# Power_SchematicWITHFOOTPRINTS.net
KiCad netlist of a schematic drawn in Altium Designer
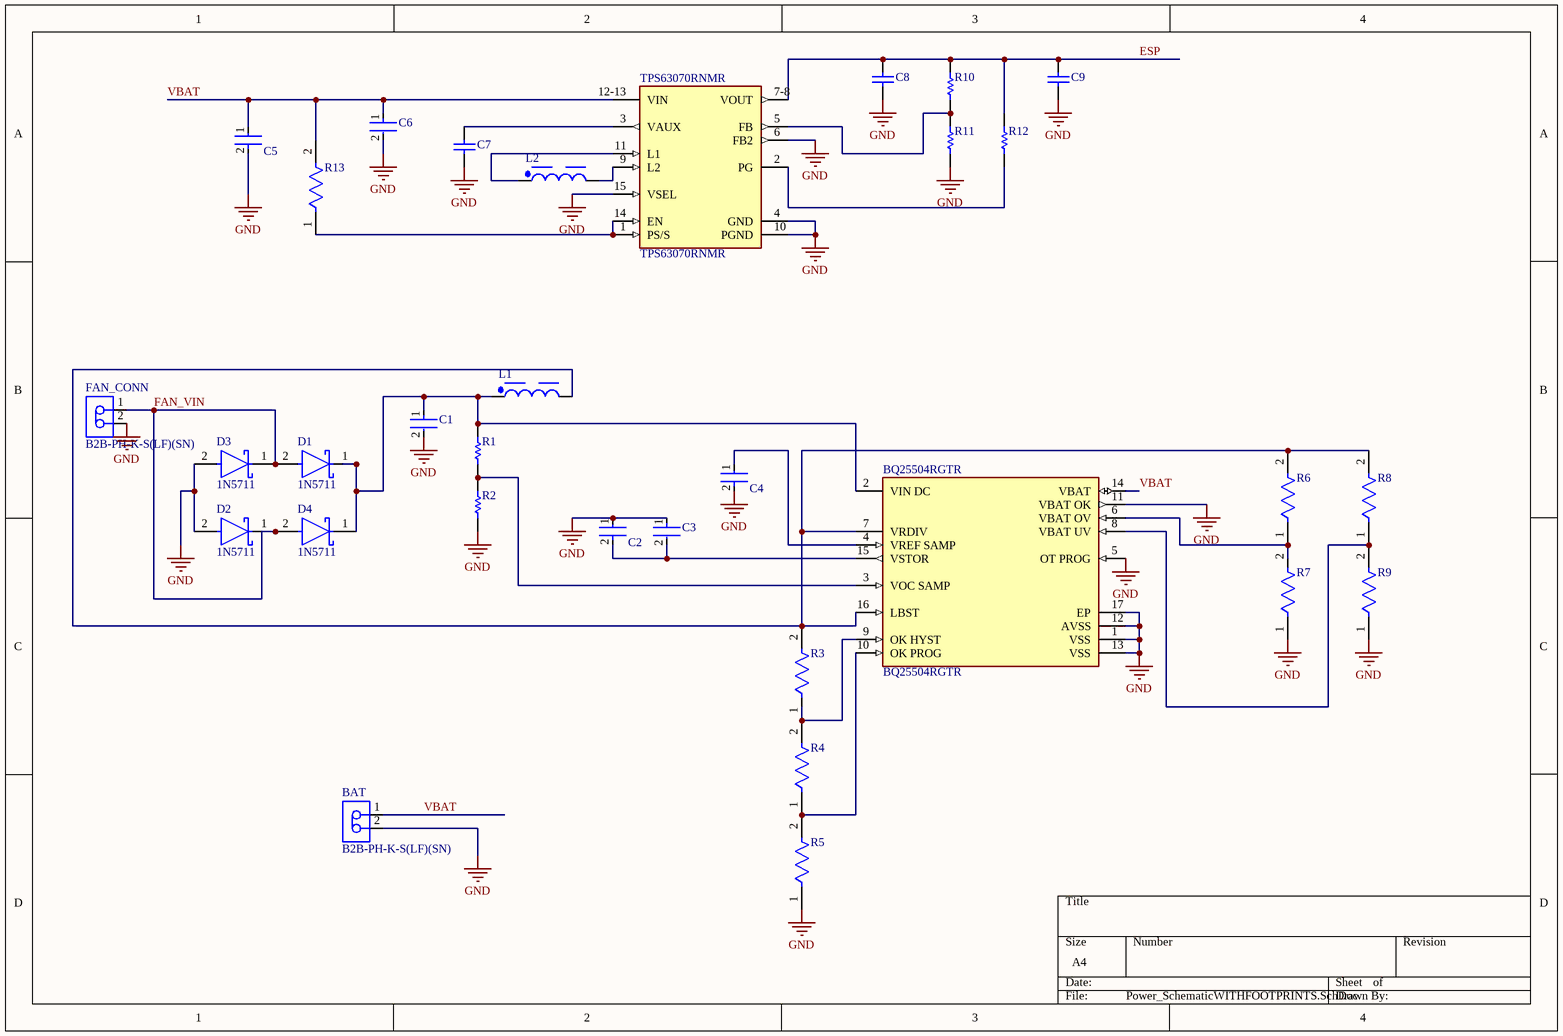
[diagram p0: Power_SchematicWITHFOOTPRINTS.SchDoc]

(export (version "E")
  (design (tool "Eeschema 10.0.6"))
  (components
    (comp (ref "BAT")
      (value "B2B-PH-K-S(LF)(SN)")
      (footprint "JST-B2B-PH-K-S_V")
      (fields (field (name "MANUFACTURER") "JST"))
      (libsource (lib "Altium Content Vault") (part "CN-2P-F-QF2"))
    )
    (comp (ref "BQ25504RGTR")
      (value "BQ25504RGTR")
      (footprint "FP-RGT0016C-IPC_B")
      (description "IC ENERGY HARV CTRLR BATT 16QFN")
      (libsource (lib "Altium Content Vault") (part "e5d8dc60ace48e978414c9197b193df"))
    )
    (comp (ref "C1")
      (value "RCER71E475K2DBH03A")
      (footprint "FP-RCE2A2-MFG")
      (description "Cap Ceramic 4.7uF 25V X7R ±10% Radial 2.5mm +125°C Automotive Ammo Pack")
      (fields (field (name "TOLERANCE") "10%"))
      (libsource (lib "Altium Content Vault") (part "b4654b650e69147ec39a6b967a45e02"))
    )
    (comp (ref "C2")
      (value "562R5GAS10")
      (footprint "FP-562R5GAS10-MFG")
      (description "CAP CER 10000PF 1KV Z5U RADIAL")
      (fields (field (name "TOLERANCE") "20%") (field (name "VOLTAGE") "1kV"))
      (libsource (lib "Altium Content Vault") (part "6d4d395cd7362dd47ce0157d173177e"))
    )
    (comp (ref "C3")
      (value "RCER71E475K2DBH03A")
      (footprint "FP-RCE2A2-MFG")
      (description "Cap Ceramic 4.7uF 25V X7R ±10% Radial 2.5mm +125°C Automotive Ammo Pack")
      (fields (field (name "TOLERANCE") "10%"))
      (libsource (lib "Altium Content Vault") (part "b4654b650e69147ec39a6b967a45e02"))
    )
    (comp (ref "C4")
      (value "562R5GAS10")
      (footprint "FP-562R5GAS10-MFG")
      (description "CAP CER 10000PF 1KV Z5U RADIAL")
      (fields (field (name "TOLERANCE") "20%") (field (name "VOLTAGE") "1kV"))
      (libsource (lib "Altium Content Vault") (part "6d4d395cd7362dd47ce0157d173177e"))
    )
    (comp (ref "C5")
      (value "562R5GAS10")
      (footprint "FP-562R5GAS10-MFG")
      (description "CAP CER 10000PF 1KV Z5U RADIAL")
      (fields (field (name "TOLERANCE") "20%") (field (name "VOLTAGE") "1kV"))
      (libsource (lib "Altium Content Vault") (part "6d4d395cd7362dd47ce0157d173177e"))
    )
    (comp (ref "C6")
      (value "RCER71E106K3DBH03A")
      (footprint "FP-RCE3DB-MFG")
      (description "Cap Ceramic 10uF 25V X7R ±10% Radial 2.5mm +125°C Automotive Ammo Pack")
      (fields (field (name "TOLERANCE") "10%"))
      (libsource (lib "Altium Content Vault") (part "b4654b650e69147ec39a6b967a45e02"))
    )
    (comp (ref "C7")
      (value "C320C104K5R5TA")
      (footprint "CAPR51-254-508X318X736")
      (libsource (lib "Altium Content Vault") (part "CAP-NP-2"))
    )
    (comp (ref "C8")
      (value "C320C104K5R5TA")
      (footprint "CAPR51-254-508X318X736")
      (libsource (lib "Altium Content Vault") (part "CAP-NP-2"))
    )
    (comp (ref "C9")
      (value "C320C104K5R5TA")
      (footprint "CAPR51-254-508X318X736")
      (libsource (lib "Altium Content Vault") (part "CAP-NP-2"))
    )
    (comp (ref "D1")
      (value "1N5711")
      (footprint "FP-DO-35-MFG")
      (description "RF DIODE SCHOTTKY 70V 430MW DO35")
      (fields
        (field (name "MANUFACTURER") "STMicroelectronics")
        (field (name "OCTOPART") "https://octopart.com/1n5711-stmicroelectronics-55399277")
      )
      (libsource (lib "Altium Content Vault") (part "1d6ec82d83fb6aee721767c19dac4b9"))
    )
    (comp (ref "D2")
      (value "1N5711")
      (footprint "FP-DO-35-MFG")
      (description "RF DIODE SCHOTTKY 70V 430MW DO35")
      (fields
        (field (name "MANUFACTURER") "STMicroelectronics")
        (field (name "OCTOPART") "https://octopart.com/1n5711-stmicroelectronics-55399277")
      )
      (libsource (lib "Altium Content Vault") (part "1d6ec82d83fb6aee721767c19dac4b9"))
    )
    (comp (ref "D3")
      (value "1N5711")
      (footprint "FP-DO-35-MFG")
      (description "RF DIODE SCHOTTKY 70V 430MW DO35")
      (fields
        (field (name "MANUFACTURER") "STMicroelectronics")
        (field (name "OCTOPART") "https://octopart.com/1n5711-stmicroelectronics-55399277")
      )
      (libsource (lib "Altium Content Vault") (part "1d6ec82d83fb6aee721767c19dac4b9"))
    )
    (comp (ref "D4")
      (value "1N5711")
      (footprint "FP-DO-35-MFG")
      (description "RF DIODE SCHOTTKY 70V 430MW DO35")
      (fields
        (field (name "MANUFACTURER") "STMicroelectronics")
        (field (name "OCTOPART") "https://octopart.com/1n5711-stmicroelectronics-55399277")
      )
      (libsource (lib "Altium Content Vault") (part "1d6ec82d83fb6aee721767c19dac4b9"))
    )
    (comp (ref "FAN_CONN")
      (value "B2B-PH-K-S(LF)(SN)")
      (footprint "JST-B2B-PH-K-S_V")
      (fields (field (name "MANUFACTURER") "JST"))
      (libsource (lib "Altium Content Vault") (part "CN-2P-F-QF2"))
    )
    (comp (ref "L1")
      (value "7447471033")
      (footprint "WE-TIS_1111")
      (fields (field (name "TOLERANCE") "20%"))
      (libsource (lib "Altium Content Vault") (part "Inductor - 2"))
    )
    (comp (ref "L2")
      (value "744741221")
      (footprint "WE-TI_8055")
      (libsource (lib "Altium Content Vault") (part "Inductor - 2"))
    )
    (comp (ref "R1")
      (value "PR02000206202JA100")
      (footprint "VISH-A1-2_V2")
      (description "Power Metal Film Leaded Resistor, 62 KOhm +/-5%, 2 W, 2-Pin THD, RoHS, Ammo Pack")
      (fields (field (name "TOLERANCE") "+/-5%") (field (name "POWER") "2 W"))
      (libsource (lib "Altium Content Vault") (part "VISH-RES-2"))
    )
    (comp (ref "R2")
      (value "PR02000206202JA100")
      (footprint "VISH-A1-2_V2")
      (description "Power Metal Film Leaded Resistor, 62 KOhm +/-5%, 2 W, 2-Pin THD, RoHS, Ammo Pack")
      (fields (field (name "TOLERANCE") "+/-5%") (field (name "POWER") "2 W"))
      (libsource (lib "Altium Content Vault") (part "VISH-RES-2"))
    )
    (comp (ref "R3")
      (value "MRS25000C1000FRP00")
      (footprint "FP-MRS25-MFG")
      (fields (field (name "TOLERANCE") "1%"))
      (libsource (lib "Altium Content Vault") (part "1029c3af85768c4190bb7ad29bc67b5"))
    )
    (comp (ref "R4")
      (value "MRS25000C1000FRP00")
      (footprint "FP-MRS25-MFG")
      (fields (field (name "TOLERANCE") "1%"))
      (libsource (lib "Altium Content Vault") (part "1029c3af85768c4190bb7ad29bc67b5"))
    )
    (comp (ref "R5")
      (value "MRS25000C1000FRP00")
      (footprint "FP-MRS25-MFG")
      (fields (field (name "TOLERANCE") "1%"))
      (libsource (lib "Altium Content Vault") (part "1029c3af85768c4190bb7ad29bc67b5"))
    )
    (comp (ref "R6")
      (value "MRS25000C1000FRP00")
      (footprint "FP-MRS25-MFG")
      (fields (field (name "TOLERANCE") "1%"))
      (libsource (lib "Altium Content Vault") (part "1029c3af85768c4190bb7ad29bc67b5"))
    )
    (comp (ref "R7")
      (value "MRS25000C1000FRP00")
      (footprint "FP-MRS25-MFG")
      (fields (field (name "TOLERANCE") "1%"))
      (libsource (lib "Altium Content Vault") (part "1029c3af85768c4190bb7ad29bc67b5"))
    )
    (comp (ref "R8")
      (value "MRS25000C1000FRP00")
      (footprint "FP-MRS25-MFG")
      (fields (field (name "TOLERANCE") "1%"))
      (libsource (lib "Altium Content Vault") (part "1029c3af85768c4190bb7ad29bc67b5"))
    )
    (comp (ref "R9")
      (value "MRS25000C1000FRP00")
      (footprint "FP-MRS25-MFG")
      (fields (field (name "TOLERANCE") "1%"))
      (libsource (lib "Altium Content Vault") (part "1029c3af85768c4190bb7ad29bc67b5"))
    )
    (comp (ref "R10")
      (value "PR02000206202JA100")
      (footprint "VISH-A1-2_V2")
      (description "Power Metal Film Leaded Resistor, 62 KOhm +/-5%, 2 W, 2-Pin THD, RoHS, Ammo Pack")
      (fields (field (name "TOLERANCE") "+/-5%") (field (name "POWER") "2 W"))
      (libsource (lib "Altium Content Vault") (part "VISH-RES-2"))
    )
    (comp (ref "R11")
      (value "PR02000206202JA100")
      (footprint "VISH-A1-2_V2")
      (description "Power Metal Film Leaded Resistor, 62 KOhm +/-5%, 2 W, 2-Pin THD, RoHS, Ammo Pack")
      (fields (field (name "TOLERANCE") "+/-5%") (field (name "POWER") "2 W"))
      (libsource (lib "Altium Content Vault") (part "VISH-RES-2"))
    )
    (comp (ref "R12")
      (value "PR02000206202JA100")
      (footprint "VISH-A1-2_V2")
      (description "Power Metal Film Leaded Resistor, 62 KOhm +/-5%, 2 W, 2-Pin THD, RoHS, Ammo Pack")
      (fields (field (name "TOLERANCE") "+/-5%") (field (name "POWER") "2 W"))
      (libsource (lib "Altium Content Vault") (part "VISH-RES-2"))
    )
    (comp (ref "R13")
      (value "MRS25000C1002FCT00")
      (footprint "FP-MRS25-MFG")
      (fields (field (name "TOLERANCE") "1%"))
      (libsource (lib "Altium Content Vault") (part "1029c3af85768c4190bb7ad29bc67b5"))
    )
    (comp (ref "TPS63070RNMR")
      (value "TPS63070RNMR")
      (footprint "FP-RNM0015A-MFG")
      (description "IC REG BCK BST ADJ 3.6A 15VQFN")
      (libsource (lib "Altium Content Vault") (part "a4d5b1e6901c8533e317c4aea8f1b15"))
    )
  )
  (nets
    (net (code "1") (name "/ESP") (class "Default")
      (node (ref "C8") (pin "2") (pinfunction "2_2") (pintype "passive"))
      (node (ref "C9") (pin "2") (pinfunction "2_2") (pintype "passive"))
      (node (ref "R10") (pin "2") (pinfunction "2_2") (pintype "passive"))
      (node (ref "R12") (pin "2") (pinfunction "2_2") (pintype "passive"))
      (node (ref "TPS63070RNMR") (pin "7-8") (pinfunction "VOUT_7-8") (pintype "output"))
    )
    (net (code "2") (name "/FAN_VIN") (class "Default")
      (node (ref "D1") (pin "2") (pinfunction "A_2") (pintype "passive"))
      (node (ref "D2") (pin "1") (pinfunction "C_1") (pintype "passive"))
      (node (ref "D3") (pin "1") (pinfunction "C_1") (pintype "passive"))
      (node (ref "D4") (pin "2") (pinfunction "A_2") (pintype "passive"))
      (node (ref "FAN_CONN") (pin "1") (pinfunction "1_1") (pintype "passive"))
    )
    (net (code "3") (name "/VBAT") (class "Default")
      (node (ref "BAT") (pin "1") (pinfunction "1_1") (pintype "passive"))
      (node (ref "BQ25504RGTR") (pin "14") (pinfunction "VBAT_14") (pintype "bidirectional"))
      (node (ref "C5") (pin "1") (pinfunction "1_1") (pintype "passive"))
      (node (ref "C6") (pin "1") (pinfunction "1_1") (pintype "passive"))
      (node (ref "R13") (pin "2") (pinfunction "2_2") (pintype "passive"))
      (node (ref "TPS63070RNMR") (pin "12-13") (pinfunction "VIN_12-13") (pintype "power_in"))
    )
    (net (code "4") (name "GND") (class "Default")
      (node (ref "BAT") (pin "2") (pinfunction "2_2") (pintype "passive"))
      (node (ref "BQ25504RGTR") (pin "1") (pinfunction "VSS_1") (pintype "power_in"))
      (node (ref "BQ25504RGTR") (pin "11") (pinfunction "VBAT_OK_11") (pintype "output"))
      (node (ref "BQ25504RGTR") (pin "12") (pinfunction "AVSS_12") (pintype "power_in"))
      (node (ref "BQ25504RGTR") (pin "13") (pinfunction "VSS_13") (pintype "power_in"))
      (node (ref "BQ25504RGTR") (pin "17") (pinfunction "EP_17") (pintype "passive"))
      (node (ref "BQ25504RGTR") (pin "5") (pinfunction "OT_PROG_5") (pintype "input"))
      (node (ref "C1") (pin "2") (pinfunction "2_2") (pintype "passive"))
      (node (ref "C2") (pin "1") (pinfunction "1_1") (pintype "passive"))
      (node (ref "C3") (pin "1") (pinfunction "1_1") (pintype "passive"))
      (node (ref "C4") (pin "2") (pinfunction "2_2") (pintype "passive"))
      (node (ref "C5") (pin "2") (pinfunction "2_2") (pintype "passive"))
      (node (ref "C6") (pin "2") (pinfunction "2_2") (pintype "passive"))
      (node (ref "C7") (pin "1") (pinfunction "1_1") (pintype "passive"))
      (node (ref "C8") (pin "1") (pinfunction "1_1") (pintype "passive"))
      (node (ref "C9") (pin "1") (pinfunction "1_1") (pintype "passive"))
      (node (ref "D2") (pin "2") (pinfunction "A_2") (pintype "passive"))
      (node (ref "D3") (pin "2") (pinfunction "A_2") (pintype "passive"))
      (node (ref "FAN_CONN") (pin "2") (pinfunction "2_2") (pintype "passive"))
      (node (ref "R11") (pin "1") (pinfunction "1_1") (pintype "passive"))
      (node (ref "R2") (pin "1") (pinfunction "1_1") (pintype "passive"))
      (node (ref "R5") (pin "1") (pinfunction "1_1") (pintype "passive"))
      (node (ref "R7") (pin "1") (pinfunction "1_1") (pintype "passive"))
      (node (ref "R9") (pin "1") (pinfunction "1_1") (pintype "passive"))
      (node (ref "TPS63070RNMR") (pin "10") (pinfunction "PGND_10") (pintype "power_in"))
      (node (ref "TPS63070RNMR") (pin "15") (pinfunction "VSEL_15") (pintype "input"))
      (node (ref "TPS63070RNMR") (pin "4") (pinfunction "GND_4") (pintype "power_in"))
      (node (ref "TPS63070RNMR") (pin "6") (pinfunction "FB2_6") (pintype "output"))
    )
    (net (code "5") (name "Net-(BQ25504RGTR-LBST)") (class "Default")
      (node (ref "BQ25504RGTR") (pin "16") (pinfunction "LBST_16") (pintype "input"))
      (node (ref "BQ25504RGTR") (pin "7") (pinfunction "VRDIV_7") (pintype "power_in"))
      (node (ref "L1") (pin "2") (pinfunction "2_2") (pintype "passive"))
      (node (ref "R3") (pin "2") (pinfunction "2_2") (pintype "passive"))
      (node (ref "R6") (pin "2") (pinfunction "2_2") (pintype "passive"))
      (node (ref "R8") (pin "2") (pinfunction "2_2") (pintype "passive"))
    )
    (net (code "6") (name "Net-(BQ25504RGTR-OK_HYST)") (class "Default")
      (node (ref "BQ25504RGTR") (pin "9") (pinfunction "OK_HYST_9") (pintype "input"))
      (node (ref "R3") (pin "1") (pinfunction "1_1") (pintype "passive"))
      (node (ref "R4") (pin "2") (pinfunction "2_2") (pintype "passive"))
    )
    (net (code "7") (name "Net-(BQ25504RGTR-OK_PROG)") (class "Default")
      (node (ref "BQ25504RGTR") (pin "10") (pinfunction "OK_PROG_10") (pintype "input"))
      (node (ref "R4") (pin "1") (pinfunction "1_1") (pintype "passive"))
      (node (ref "R5") (pin "2") (pinfunction "2_2") (pintype "passive"))
    )
    (net (code "8") (name "Net-(BQ25504RGTR-VBAT_OV)") (class "Default")
      (node (ref "BQ25504RGTR") (pin "6") (pinfunction "VBAT_OV_6") (pintype "input"))
      (node (ref "R6") (pin "1") (pinfunction "1_1") (pintype "passive"))
      (node (ref "R7") (pin "2") (pinfunction "2_2") (pintype "passive"))
    )
    (net (code "9") (name "Net-(BQ25504RGTR-VBAT_UV)") (class "Default")
      (node (ref "BQ25504RGTR") (pin "8") (pinfunction "VBAT_UV_8") (pintype "input"))
      (node (ref "R8") (pin "1") (pinfunction "1_1") (pintype "passive"))
      (node (ref "R9") (pin "2") (pinfunction "2_2") (pintype "passive"))
    )
    (net (code "10") (name "Net-(BQ25504RGTR-VIN_DC)") (class "Default")
      (node (ref "BQ25504RGTR") (pin "2") (pinfunction "VIN_DC_2") (pintype "power_in"))
      (node (ref "C1") (pin "1") (pinfunction "1_1") (pintype "passive"))
      (node (ref "D1") (pin "1") (pinfunction "C_1") (pintype "passive"))
      (node (ref "D4") (pin "1") (pinfunction "C_1") (pintype "passive"))
      (node (ref "L1") (pin "1") (pinfunction "1_1") (pintype "passive"))
      (node (ref "R1") (pin "2") (pinfunction "2_2") (pintype "passive"))
    )
    (net (code "11") (name "Net-(BQ25504RGTR-VOC_SAMP)") (class "Default")
      (node (ref "BQ25504RGTR") (pin "3") (pinfunction "VOC_SAMP_3") (pintype "input"))
      (node (ref "R1") (pin "1") (pinfunction "1_1") (pintype "passive"))
      (node (ref "R2") (pin "2") (pinfunction "2_2") (pintype "passive"))
    )
    (net (code "12") (name "Net-(BQ25504RGTR-VREF_SAMP)") (class "Default")
      (node (ref "BQ25504RGTR") (pin "4") (pinfunction "VREF_SAMP_4") (pintype "input"))
      (node (ref "C4") (pin "1") (pinfunction "1_1") (pintype "passive"))
    )
    (net (code "13") (name "Net-(BQ25504RGTR-VSTOR)") (class "Default")
      (node (ref "BQ25504RGTR") (pin "15") (pinfunction "VSTOR_15") (pintype "output"))
      (node (ref "C2") (pin "2") (pinfunction "2_2") (pintype "passive"))
      (node (ref "C3") (pin "2") (pinfunction "2_2") (pintype "passive"))
    )
    (net (code "14") (name "Net-(TPS63070RNMR-EN)") (class "Default")
      (node (ref "R13") (pin "1") (pinfunction "1_1") (pintype "passive"))
      (node (ref "TPS63070RNMR") (pin "1") (pinfunction "PS/S_1") (pintype "input"))
      (node (ref "TPS63070RNMR") (pin "14") (pinfunction "EN_14") (pintype "input"))
    )
    (net (code "15") (name "Net-(TPS63070RNMR-FB)") (class "Default")
      (node (ref "R10") (pin "1") (pinfunction "1_1") (pintype "passive"))
      (node (ref "R11") (pin "2") (pinfunction "2_2") (pintype "passive"))
      (node (ref "TPS63070RNMR") (pin "5") (pinfunction "FB_5") (pintype "output"))
    )
    (net (code "16") (name "Net-(TPS63070RNMR-L1)") (class "Default")
      (node (ref "L2") (pin "1") (pinfunction "1_1") (pintype "passive"))
      (node (ref "TPS63070RNMR") (pin "11") (pinfunction "L1_11") (pintype "input"))
    )
    (net (code "17") (name "Net-(TPS63070RNMR-L2)") (class "Default")
      (node (ref "L2") (pin "2") (pinfunction "2_2") (pintype "passive"))
      (node (ref "TPS63070RNMR") (pin "9") (pinfunction "L2_9") (pintype "input"))
    )
    (net (code "18") (name "Net-(TPS63070RNMR-PG)") (class "Default")
      (node (ref "R12") (pin "1") (pinfunction "1_1") (pintype "passive"))
      (node (ref "TPS63070RNMR") (pin "2") (pinfunction "PG_2") (pintype "open_collector"))
    )
    (net (code "19") (name "Net-(TPS63070RNMR-VAUX)") (class "Default")
      (node (ref "C7") (pin "2") (pinfunction "2_2") (pintype "passive"))
      (node (ref "TPS63070RNMR") (pin "3") (pinfunction "VAUX_3") (pintype "output"))
    )
  )
)
